# ARM_LM3670_1_3.net
KiCad netlist of a schematic drawn in Altium Designer
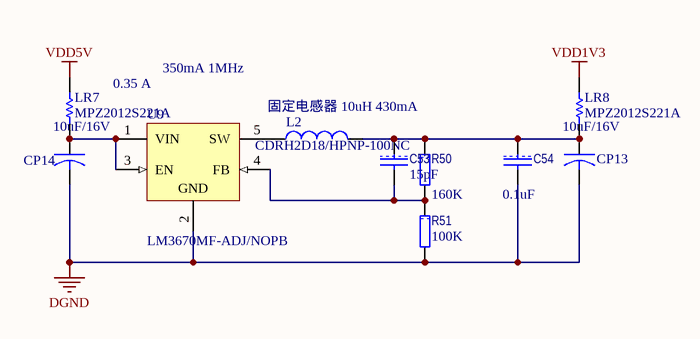
[diagram p0: 电源ARM_LM3670_1.3.SchDoc]

(export (version "E")
  (design (tool "Eeschema 10.0.6"))
  (components
    (comp (ref "C53")
      (value "15pF")
      (footprint "1608[0603]C")
      (description "多层陶瓷电容器MLCC - SMD/SMT 0603 15pF 50volts C0G 5%")
      (fields (field (name "MANUFACTURER") "TDK") (field (name "MANUFACTURER PART NUMBER") "C1608C0G1H150J"))
      (libsource (lib "*") (part "CAP"))
    )
    (comp (ref "C54")
      (value "0.1uF")
      (footprint "1608[0603]C")
      (description "多层陶瓷电容器MLCC - SMD/SMT 0603 0.1uF 50volts X7R 10%")
      (fields (field (name "MANUFACTURER") "TDK") (field (name "MANUFACTURER PART NUMBER") "C1608X7R1H104K"))
      (libsource (lib "*") (part "CAP"))
    )
    (comp (ref "CP13")
      (value "10uF/16V")
      (footprint "3216[1206]CB")
      (description "钽质电容器-固体SMD 16volts 10uF 10%")
      (fields (field (name "MANUFACTURER") "AVX") (field (name "MANUFACTURER PART NUMBER") "TAJA106K016RNJ"))
      (libsource (lib "*") (part "CAPACITOR"))
    )
    (comp (ref "CP14")
      (value "10uF/16V")
      (footprint "3216[1206]CB")
      (description "钽质电容器-固体SMD 16volts 10uF 10%")
      (fields (field (name "MANUFACTURER") "AVX") (field (name "MANUFACTURER PART NUMBER") "TAJA106K016RNJ"))
      (libsource (lib "*") (part "CAPACITOR"))
    )
    (comp (ref "L2")
      (value "CDRH2D18/HPNP-100NC")
      (footprint "INDP3232")
      (description "固定电感器 10uH 430mA")
      (fields (field (name "MANUFACTURER") "Sumida") (field (name "DESCRIPTION 1") "固定电感器 10uH 430mA"))
      (libsource (lib "Miscellaneous Devices") (part "Inductor"))
    )
    (comp (ref "LR7")
      (value "MPZ2012S221A")
      (footprint "2012[0805]")
      (description "电磁干扰滤波珠子、扼流圈和阵列 Ferrite Chip Beads")
      (fields (field (name "MANUFACTURER") "TDK"))
      (libsource (lib "Miscellaneous Devices") (part "Res Semi"))
    )
    (comp (ref "LR8")
      (value "MPZ2012S221A")
      (footprint "2012[0805]")
      (description "电磁干扰滤波珠子、扼流圈和阵列 Ferrite Chip Beads")
      (fields (field (name "MANUFACTURER") "TDK"))
      (libsource (lib "Miscellaneous Devices") (part "Res Semi"))
    )
    (comp (ref "R50")
      (value "160K")
      (footprint "1608[0603]R")
      (description "薄膜电阻器 - SMD 160Kohms .1% 25ppm")
      (fields
        (field (name "MANUFACTURER") "Vishay")
        (field (name "MANUFACTURER PART NUMBER") "TNPW0805160KBEEN")
      )
      (libsource (lib "10K 1%") (part "RES"))
    )
    (comp (ref "R51")
      (value "100K")
      (footprint "1608[0603]R")
      (description "厚膜电阻器 - SMD 1/10watt 100Kohms 1%")
      (fields
        (field (name "MANUFACTURER") "Vishay / Dale")
        (field (name "MANUFACTURER PART NUMBER") "CRCW0603100KFKEA")
      )
      (libsource (lib "100K 1%") (part "RES"))
    )
    (comp (ref "U9")
      (value "LM3670MF-ADJ/NOPB")
      (footprint "SOT23-5BN")
      (description "DC/DC 开关控制器 Mini SD DC-DC Cnvtr")
      (fields (field (name "MANUFACTURER") "Texas Instruments") (field (name "ÊÄ³ÖΜÇÁ÷") "0.35 A"))
      (libsource (lib "NSC Switcher") (part "LM3670MF-3.3/NOPB"))
    )
  )
  (nets
    (net (code "1") (name "DGND") (class "Default")
      (node (ref "C54") (pin "2") (pinfunction "2_2") (pintype "passive"))
      (node (ref "CP13") (pin "2") (pinfunction "2_2") (pintype "passive"))
      (node (ref "CP14") (pin "2") (pinfunction "2_2") (pintype "passive"))
      (node (ref "R51") (pin "2") (pinfunction "2_2") (pintype "passive"))
      (node (ref "U9") (pin "2") (pinfunction "GND_2") (pintype "power_in"))
    )
    (net (code "2") (name "Net-(C53-Pad1)") (class "Default")
      (node (ref "C53") (pin "1") (pinfunction "1_1") (pintype "passive"))
      (node (ref "C54") (pin "1") (pinfunction "1_1") (pintype "passive"))
      (node (ref "CP13") (pin "1") (pinfunction "1_1") (pintype "passive"))
      (node (ref "L2") (pin "2") (pinfunction "2_2") (pintype "passive"))
      (node (ref "LR8") (pin "1") (pinfunction "1_1") (pintype "passive"))
      (node (ref "R50") (pin "1") (pinfunction "1_1") (pintype "passive"))
    )
    (net (code "3") (name "Net-(U9-EN)") (class "Default")
      (node (ref "CP14") (pin "1") (pinfunction "1_1") (pintype "passive"))
      (node (ref "LR7") (pin "1") (pinfunction "1_1") (pintype "passive"))
      (node (ref "U9") (pin "1") (pinfunction "VIN_1") (pintype "power_in"))
      (node (ref "U9") (pin "3") (pinfunction "EN_3") (pintype "input"))
    )
    (net (code "4") (name "Net-(U9-FB)") (class "Default")
      (node (ref "C53") (pin "2") (pinfunction "2_2") (pintype "passive"))
      (node (ref "R50") (pin "2") (pinfunction "2_2") (pintype "passive"))
      (node (ref "R51") (pin "1") (pinfunction "1_1") (pintype "passive"))
      (node (ref "U9") (pin "4") (pinfunction "FB_4") (pintype "input"))
    )
    (net (code "5") (name "Net-(U9-SW)") (class "Default")
      (node (ref "L2") (pin "1") (pinfunction "1_1") (pintype "passive"))
      (node (ref "U9") (pin "5") (pinfunction "SW_5") (pintype "power_in"))
    )
    (net (code "6") (name "VDD1V3") (class "Default")
      (node (ref "LR8") (pin "2") (pinfunction "2_2") (pintype "passive"))
    )
    (net (code "7") (name "VDD5V") (class "Default")
      (node (ref "LR7") (pin "2") (pinfunction "2_2") (pintype "passive"))
    )
  )
)
